# 09-TESTPOINTS.net
KiCad netlist of a schematic drawn in Altium Designer
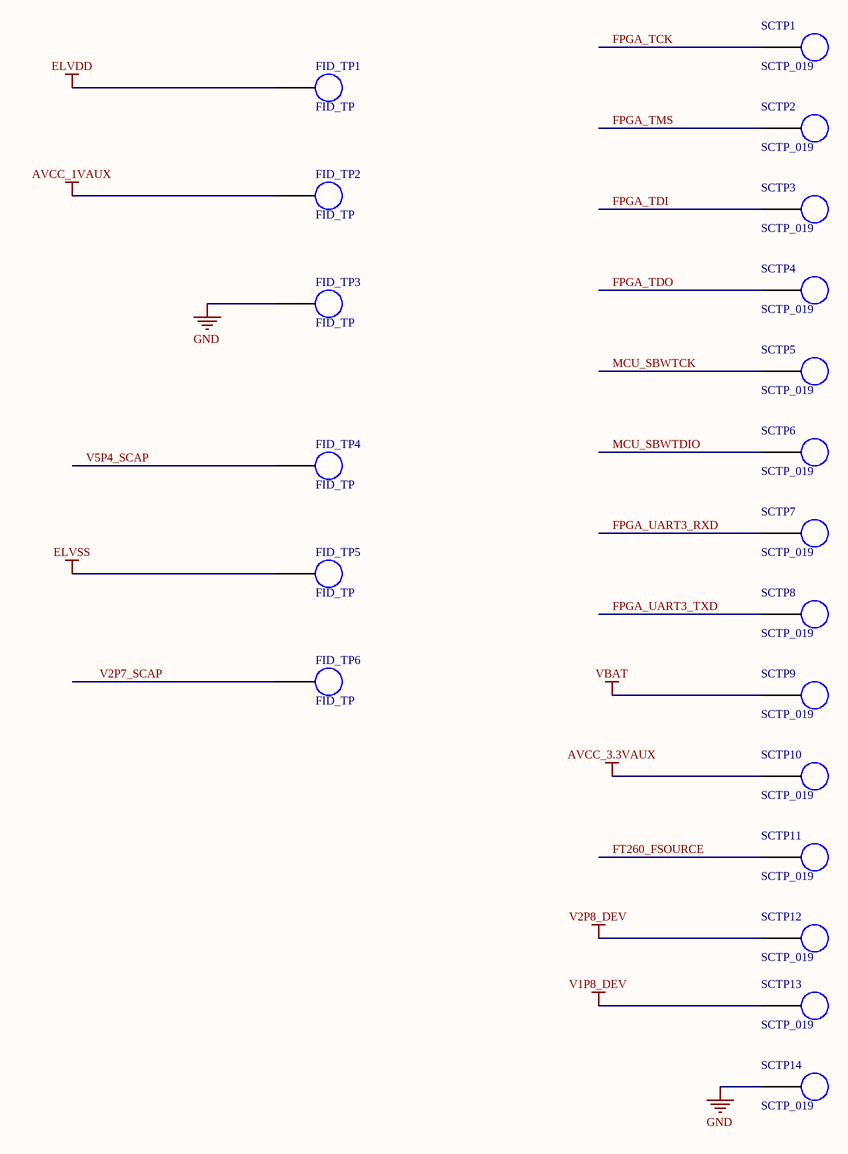
[diagram p0: 09-TESTPOINTS.SchDoc]

(export (version "E")
  (design (tool "Eeschema 10.0.6"))
  (components
    (comp (ref "FID_TP1")
      (value "FID_TP")
      (footprint "FID_TP")
      (description "Fiducial Testpoint")
      (libsource (lib "PSD_V2_Schlib") (part "FID_TP"))
    )
    (comp (ref "FID_TP2")
      (value "FID_TP")
      (footprint "FID_TP")
      (description "Fiducial Testpoint")
      (libsource (lib "PSD_V2_Schlib") (part "FID_TP"))
    )
    (comp (ref "FID_TP3")
      (value "FID_TP")
      (footprint "FID_TP")
      (description "Fiducial Testpoint")
      (libsource (lib "PSD_V2_Schlib") (part "FID_TP"))
    )
    (comp (ref "FID_TP4")
      (value "FID_TP")
      (footprint "FID_TP")
      (description "Fiducial Testpoint")
      (libsource (lib "PSD_V2_Schlib") (part "FID_TP"))
    )
    (comp (ref "FID_TP5")
      (value "FID_TP")
      (footprint "FID_TP")
      (description "Fiducial Testpoint")
      (libsource (lib "PSD_V2_Schlib") (part "FID_TP"))
    )
    (comp (ref "FID_TP6")
      (value "FID_TP")
      (footprint "FID_TP")
      (description "Fiducial Testpoint")
      (libsource (lib "PSD_V2_Schlib") (part "FID_TP"))
    )
    (comp (ref "SCTP1")
      (value "SCTP_019")
      (footprint "SCTP_019")
      (description "0.019\" Spring Contact Testpoint")
      (libsource (lib "PSD_V2_Schlib") (part "SCTP_019"))
    )
    (comp (ref "SCTP2")
      (value "SCTP_019")
      (footprint "SCTP_019")
      (description "0.019\" Spring Contact Testpoint")
      (libsource (lib "PSD_V2_Schlib") (part "SCTP_019"))
    )
    (comp (ref "SCTP3")
      (value "SCTP_019")
      (footprint "SCTP_019")
      (description "0.019\" Spring Contact Testpoint")
      (libsource (lib "PSD_V2_Schlib") (part "SCTP_019"))
    )
    (comp (ref "SCTP4")
      (value "SCTP_019")
      (footprint "SCTP_019")
      (description "0.019\" Spring Contact Testpoint")
      (libsource (lib "PSD_V2_Schlib") (part "SCTP_019"))
    )
    (comp (ref "SCTP5")
      (value "SCTP_019")
      (footprint "SCTP_019")
      (description "0.019\" Spring Contact Testpoint")
      (libsource (lib "PSD_V2_Schlib") (part "SCTP_019"))
    )
    (comp (ref "SCTP6")
      (value "SCTP_019")
      (footprint "SCTP_019")
      (description "0.019\" Spring Contact Testpoint")
      (libsource (lib "PSD_V2_Schlib") (part "SCTP_019"))
    )
    (comp (ref "SCTP7")
      (value "SCTP_019")
      (footprint "SCTP_019")
      (description "0.019\" Spring Contact Testpoint")
      (libsource (lib "PSD_V2_Schlib") (part "SCTP_019"))
    )
    (comp (ref "SCTP8")
      (value "SCTP_019")
      (footprint "SCTP_019")
      (description "0.019\" Spring Contact Testpoint")
      (libsource (lib "PSD_V2_Schlib") (part "SCTP_019"))
    )
    (comp (ref "SCTP9")
      (value "SCTP_019")
      (footprint "SCTP_019")
      (description "0.019\" Spring Contact Testpoint")
      (libsource (lib "PSD_V2_Schlib") (part "SCTP_019"))
    )
    (comp (ref "SCTP10")
      (value "SCTP_019")
      (footprint "SCTP_019")
      (description "0.019\" Spring Contact Testpoint")
      (libsource (lib "PSD_V2_Schlib") (part "SCTP_019"))
    )
    (comp (ref "SCTP11")
      (value "SCTP_019")
      (footprint "SCTP_019")
      (description "0.019\" Spring Contact Testpoint")
      (libsource (lib "PSD_V2_Schlib") (part "SCTP_019"))
    )
    (comp (ref "SCTP12")
      (value "SCTP_019")
      (footprint "SCTP_019")
      (description "0.019\" Spring Contact Testpoint")
      (libsource (lib "PSD_V2_Schlib") (part "SCTP_019"))
    )
    (comp (ref "SCTP13")
      (value "SCTP_019")
      (footprint "SCTP_019")
      (description "0.019\" Spring Contact Testpoint")
      (libsource (lib "PSD_V2_Schlib") (part "SCTP_019"))
    )
    (comp (ref "SCTP14")
      (value "SCTP_019")
      (footprint "SCTP_019")
      (description "0.019\" Spring Contact Testpoint")
      (libsource (lib "PSD_V2_Schlib") (part "SCTP_019"))
    )
  )
  (nets
    (net (code "1") (name "/FPGA_TCK") (class "Default")
      (node (ref "SCTP1") (pin "SCTP") (pintype "passive"))
    )
    (net (code "2") (name "/FPGA_TDI") (class "Default")
      (node (ref "SCTP3") (pin "SCTP") (pintype "passive"))
    )
    (net (code "3") (name "/FPGA_TDO") (class "Default")
      (node (ref "SCTP4") (pin "SCTP") (pintype "passive"))
    )
    (net (code "4") (name "/FPGA_TMS") (class "Default")
      (node (ref "SCTP2") (pin "SCTP") (pintype "passive"))
    )
    (net (code "5") (name "/FPGA_UART3_RXD") (class "Default")
      (node (ref "SCTP7") (pin "SCTP") (pintype "passive"))
    )
    (net (code "6") (name "/FPGA_UART3_TXD") (class "Default")
      (node (ref "SCTP8") (pin "SCTP") (pintype "passive"))
    )
    (net (code "7") (name "/FT260_FSOURCE") (class "Default")
      (node (ref "SCTP11") (pin "SCTP") (pintype "passive"))
    )
    (net (code "8") (name "/MCU_SBWTCK") (class "Default")
      (node (ref "SCTP5") (pin "SCTP") (pintype "passive"))
    )
    (net (code "9") (name "/MCU_SBWTDIO") (class "Default")
      (node (ref "SCTP6") (pin "SCTP") (pintype "passive"))
    )
    (net (code "10") (name "/V2P7_SCAP") (class "Default")
      (node (ref "FID_TP6") (pin "TP") (pintype "passive"))
    )
    (net (code "11") (name "/V5P4_SCAP") (class "Default")
      (node (ref "FID_TP4") (pin "TP") (pintype "passive"))
    )
    (net (code "12") (name "AVCC_1VAUX") (class "Default")
      (node (ref "FID_TP2") (pin "TP") (pintype "passive"))
    )
    (net (code "13") (name "AVCC_3.3VAUX") (class "Default")
      (node (ref "SCTP10") (pin "SCTP") (pintype "passive"))
    )
    (net (code "14") (name "ELVDD") (class "Default") (node (ref "FID_TP1") (pin "TP") (pintype "passive")))
    (net (code "15") (name "ELVSS") (class "Default") (node (ref "FID_TP5") (pin "TP") (pintype "passive")))
    (net (code "16") (name "GND") (class "Default")
      (node (ref "FID_TP3") (pin "TP") (pintype "passive"))
      (node (ref "SCTP14") (pin "SCTP") (pintype "passive"))
    )
    (net (code "17") (name "V1P8_DEV") (class "Default")
      (node (ref "SCTP13") (pin "SCTP") (pintype "passive"))
    )
    (net (code "18") (name "V2P8_DEV") (class "Default")
      (node (ref "SCTP12") (pin "SCTP") (pintype "passive"))
    )
    (net (code "19") (name "VBAT") (class "Default") (node (ref "SCTP9") (pin "SCTP") (pintype "passive")))
  )
)
